# power_routing_board.net
KiCad netlist of a schematic drawn in EAGLE
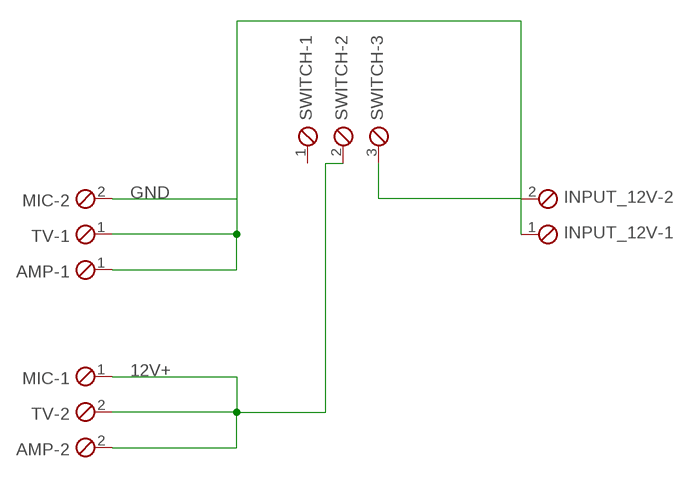
[diagram p0: schematic, sheet 1]

(export (version "E")
  (design (tool "Eeschema 10.0.6"))
  (components
    (comp (ref "AMP")
      (value "TB3POL")
      (footprint "eagle-import:2POL381")
      (libsource (lib "eagle-import") (part "MKDS1/2-3,81"))
    )
    (comp (ref "INPUT_12V")
      (value "TB3POL")
      (footprint "eagle-import:2POL381")
      (libsource (lib "eagle-import") (part "MKDS1/2-3,81"))
    )
    (comp (ref "MIC")
      (value "TB3POL")
      (footprint "eagle-import:2POL381")
      (libsource (lib "eagle-import") (part "MKDS1/2-3,81"))
    )
    (comp (ref "SWITCH")
      (value "TB3POL")
      (footprint "eagle-import:3POL381")
      (libsource (lib "eagle-import") (part "MKDS1/3-3,81"))
    )
    (comp (ref "TV")
      (value "TB3POL")
      (footprint "eagle-import:2POL381")
      (libsource (lib "eagle-import") (part "MKDS1/2-3,81"))
    )
  )
  (nets
    (net (code "1") (name "/12V+") (class "Default")
      (node (ref "AMP") (pin "2") (pinfunction "1_2") (pintype "passive"))
      (node (ref "MIC") (pin "1") (pinfunction "1_1") (pintype "passive"))
      (node (ref "SWITCH") (pin "2") (pinfunction "1_2") (pintype "passive"))
      (node (ref "TV") (pin "2") (pinfunction "1_2") (pintype "passive"))
    )
    (net (code "2") (name "/GND") (class "Default")
      (node (ref "AMP") (pin "1") (pinfunction "1_1") (pintype "passive"))
      (node (ref "INPUT_12V") (pin "1") (pinfunction "1_1") (pintype "passive"))
      (node (ref "MIC") (pin "2") (pinfunction "1_2") (pintype "passive"))
      (node (ref "TV") (pin "1") (pinfunction "1_1") (pintype "passive"))
    )
    (net (code "3") (name "Net-(INPUT_12VB-1)") (class "Default")
      (node (ref "INPUT_12V") (pin "2") (pinfunction "1_2") (pintype "passive"))
      (node (ref "SWITCH") (pin "3") (pinfunction "1_3") (pintype "passive"))
    )
    (net (code "4") (name "unconnected-(SWITCH-Pad1)") (class "Default")
      (node (ref "SWITCH") (pin "1") (pinfunction "1_1") (pintype "passive"))
    )
  )
)
